# My_esp.net
KiCad netlist of a schematic drawn in Altium Designer
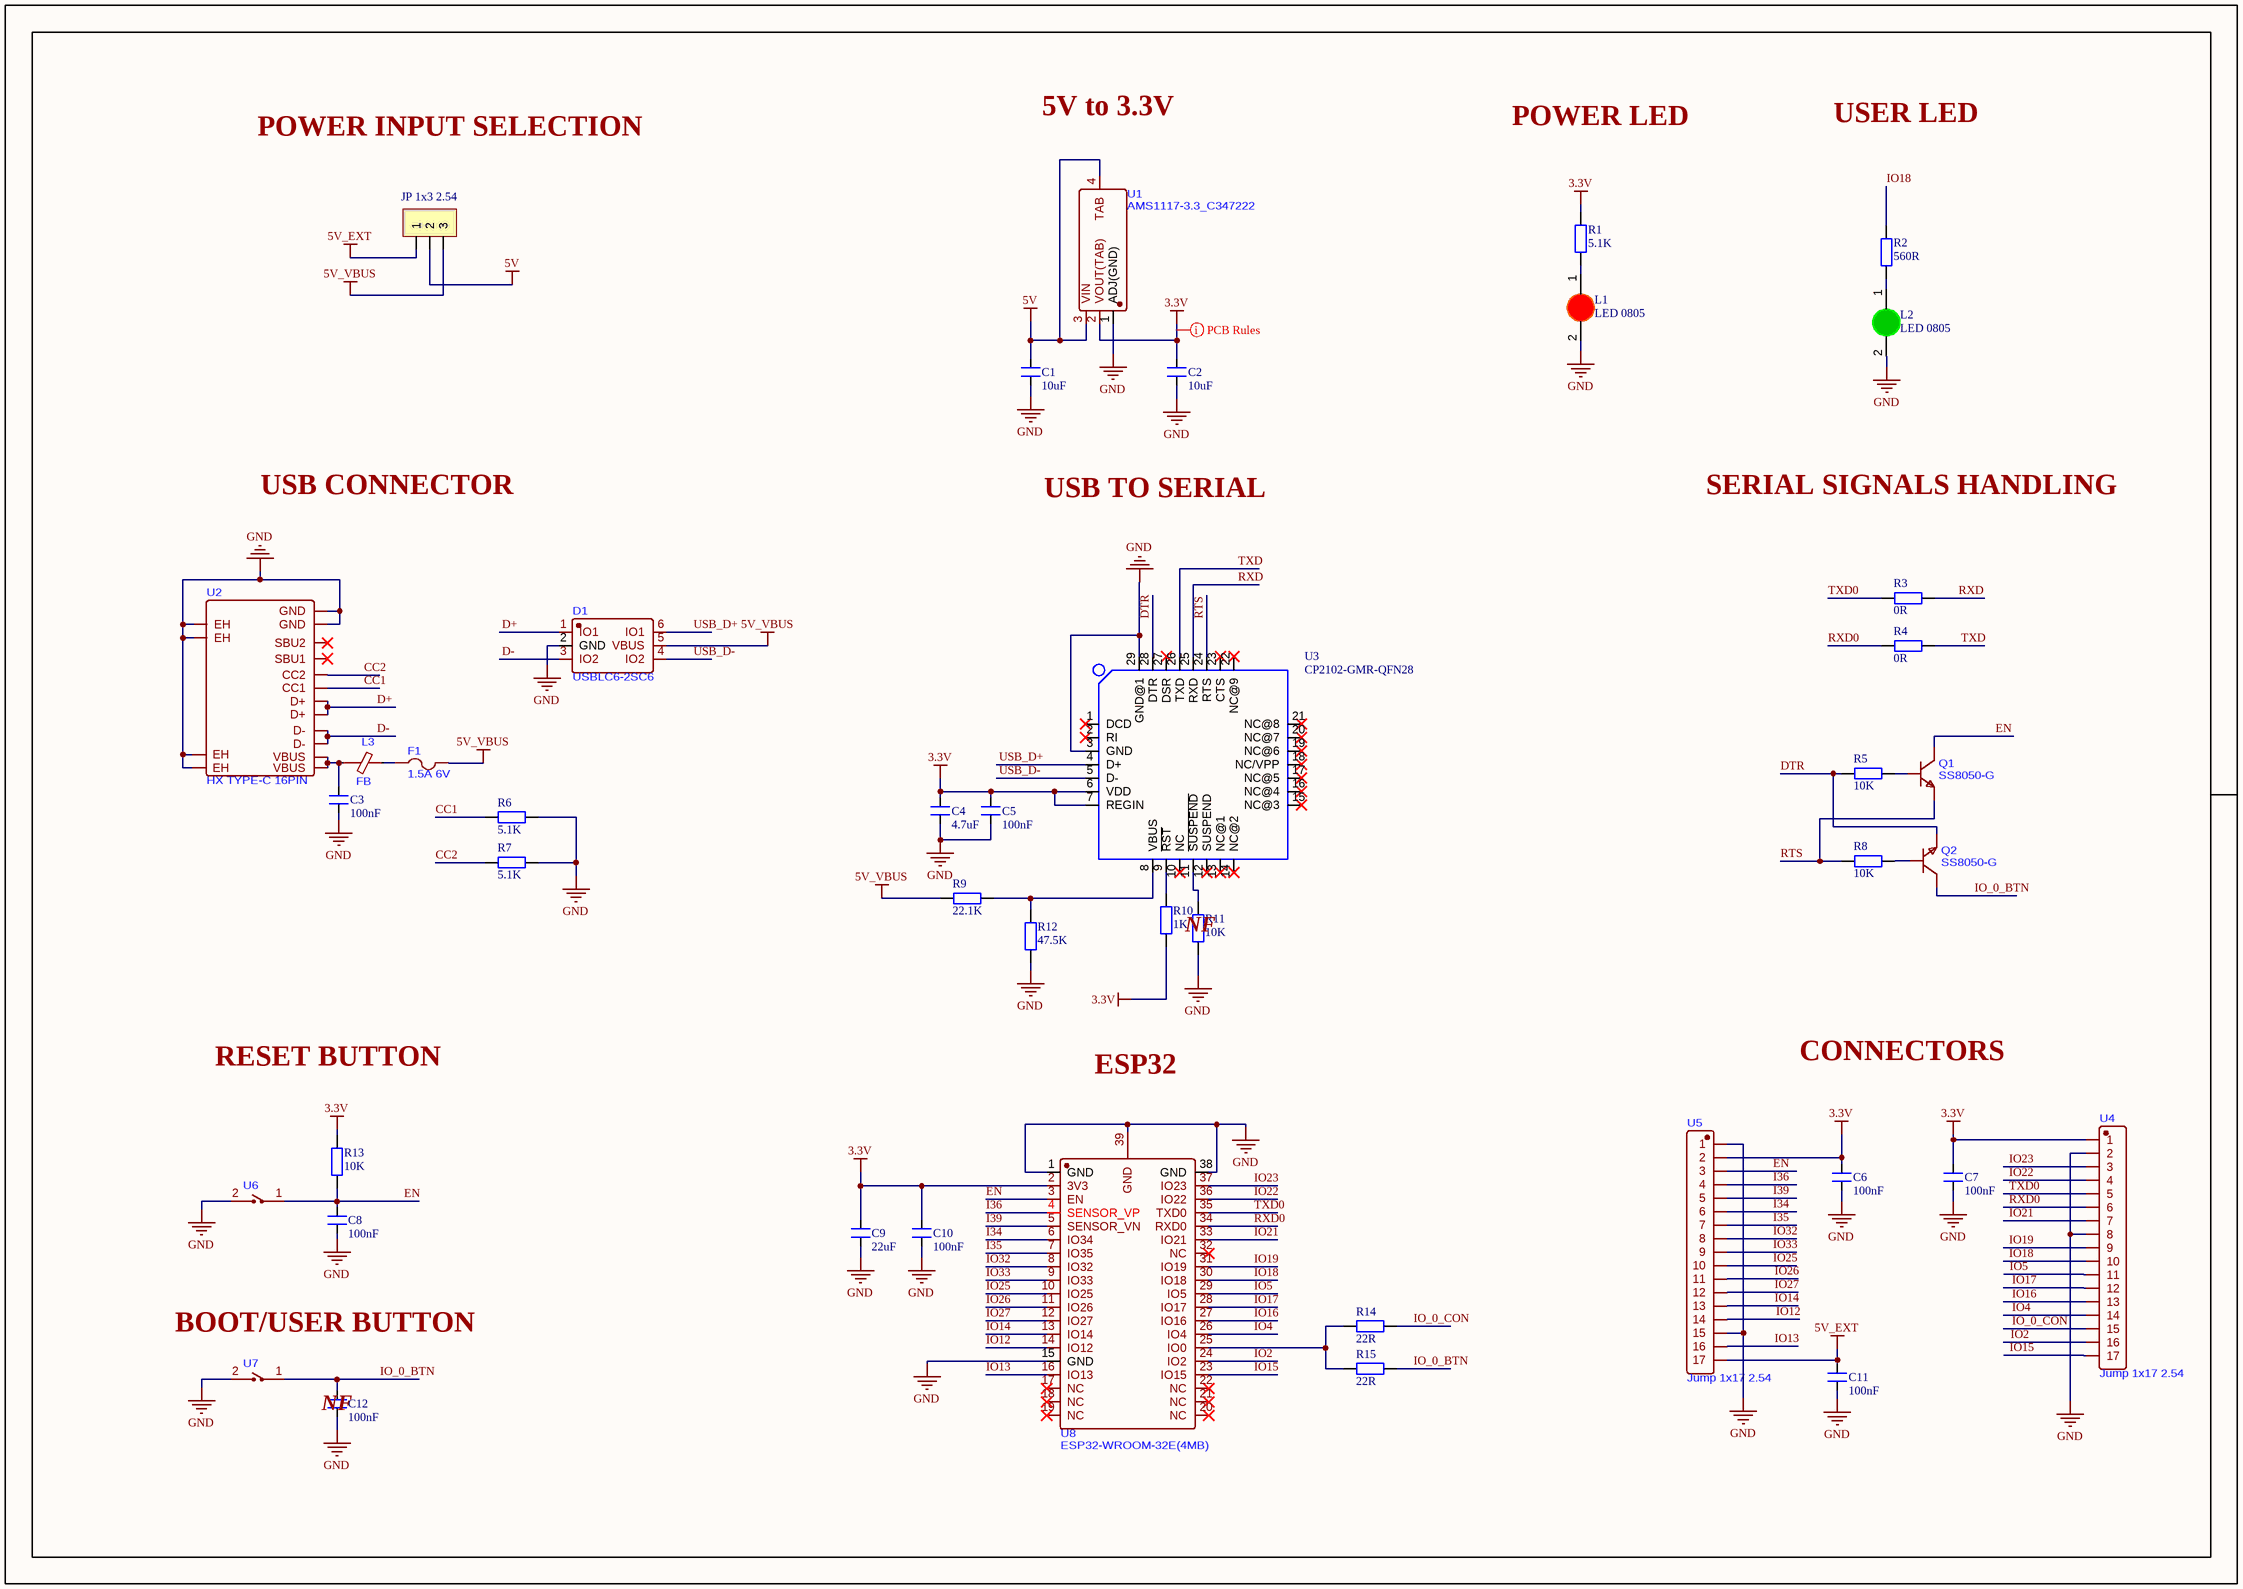
[diagram p0: My_esp.SchDoc]

(export (version "E")
  (design (tool "Eeschema 10.0.6"))
  (components
    (comp (ref "C1")
      (value "10uF")
      (footprint "SM-0805")
      (description "Cap SMD")
      (libsource (lib "My_own_ESP32") (part "Tu"))
    )
    (comp (ref "C2")
      (value "10uF")
      (footprint "SM-0805")
      (description "Cap SMD")
      (libsource (lib "My_own_ESP32") (part "Tu"))
    )
    (comp (ref "C3")
      (value "100nF")
      (footprint "SM-0805")
      (description "Cap SMD")
      (libsource (lib "My_own_ESP32") (part "Tu"))
    )
    (comp (ref "C4")
      (value "4.7uF")
      (footprint "SM-0805")
      (description "Cap SMD")
      (libsource (lib "My_own_ESP32") (part "Tu"))
    )
    (comp (ref "C5")
      (value "100nF")
      (footprint "SM-0805")
      (description "Cap SMD")
      (libsource (lib "My_own_ESP32") (part "Tu"))
    )
    (comp (ref "C6")
      (value "100nF")
      (footprint "SM-0805")
      (description "Cap SMD")
      (libsource (lib "My_own_ESP32") (part "Tu"))
    )
    (comp (ref "C7")
      (value "100nF")
      (footprint "SM-0805")
      (description "Cap SMD")
      (libsource (lib "My_own_ESP32") (part "Tu"))
    )
    (comp (ref "C8")
      (value "100nF")
      (footprint "SM-0805")
      (description "Cap SMD")
      (libsource (lib "My_own_ESP32") (part "Tu"))
    )
    (comp (ref "C9")
      (value "22uF")
      (footprint "SM-0805")
      (description "Cap SMD")
      (libsource (lib "My_own_ESP32") (part "Tu"))
    )
    (comp (ref "C10")
      (value "100nF")
      (footprint "SM-0805")
      (description "Cap SMD")
      (libsource (lib "My_own_ESP32") (part "Tu"))
    )
    (comp (ref "C11")
      (value "100nF")
      (footprint "SM-0805")
      (description "Cap SMD")
      (libsource (lib "My_own_ESP32") (part "Tu"))
    )
    (comp (ref "C12")
      (value "100nF")
      (footprint "SM-0805")
      (description "Cap SMD")
      (libsource (lib "My_own_ESP32") (part "Tu"))
    )
    (comp (ref "D1")
      (value "USBLC6-2SC6")
      (footprint "SOT-23-6_L2.9-W1.6-P0.95-LS2.8-BL")
      (libsource (lib "My_own_ESP32") (part "USBLC6-2SC6"))
    )
    (comp (ref "F1")
      (value "1.5A 6V")
      (footprint "R1206")
      (description "1.5A 6V SMD")
      (libsource (lib "My_own_ESP32") (part "Cau tri tu phuc hoi"))
    )
    (comp (ref "JP1")
      (value "JP 1x3 2.54")
      (footprint "JP 1x3 DT")
      (description "Cắm")
      (libsource (lib "Altium_Lib_by_KhueNguyenCreator") (part "JP 1x3 2.54 Duc Thang"))
    )
    (comp (ref "L1")
      (value "LED 0805")
      (footprint "LED-0805-Red")
      (description "Dán")
      (libsource (lib "Altium_Lib_by_KhueNguyenCreator") (part "LED 0805 Do"))
    )
    (comp (ref "L2")
      (value "LED 0805")
      (footprint "LED-0805-Green")
      (description "Dán")
      (libsource (lib "Altium_Lib_by_KhueNguyenCreator") (part "LED 0805 Xanh La"))
    )
    (comp (ref "L3") (value "FB") (footprint "L0805") (libsource (lib "My_own_ESP32") (part "FerriteBead")))
    (comp (ref "Q1")
      (value "SS8050-G")
      (footprint "SOT-23-3_L2.9-W1.3-P1.90-LS2.4-BR")
      (libsource (lib "My_own_ESP32") (part "SS8050-G"))
    )
    (comp (ref "Q2")
      (value "SS8050-G")
      (footprint "SOT-23-3_L2.9-W1.3-P1.90-LS2.4-BR")
      (libsource (lib "My_own_ESP32") (part "SS8050-G"))
    )
    (comp (ref "R1")
      (value "5.1K")
      (footprint "SM-0805")
      (description "Resistor SMD")
      (libsource (lib "My_own_ESP32") (part "RM"))
    )
    (comp (ref "R2")
      (value "560R")
      (footprint "SM-0805")
      (description "Resistor SMD")
      (libsource (lib "My_own_ESP32") (part "RM"))
    )
    (comp (ref "R3")
      (value "0R")
      (footprint "SM-0805")
      (description "Resistor SMD")
      (libsource (lib "My_own_ESP32") (part "RM"))
    )
    (comp (ref "R4")
      (value "0R")
      (footprint "SM-0805")
      (description "Resistor SMD")
      (libsource (lib "My_own_ESP32") (part "RM"))
    )
    (comp (ref "R5")
      (value "10K")
      (footprint "SM-0805")
      (description "Resistor SMD")
      (libsource (lib "My_own_ESP32") (part "RM"))
    )
    (comp (ref "R6")
      (value "5.1K")
      (footprint "SM-0805")
      (description "Resistor SMD")
      (libsource (lib "My_own_ESP32") (part "RM"))
    )
    (comp (ref "R7")
      (value "5.1K")
      (footprint "SM-0805")
      (description "Resistor SMD")
      (libsource (lib "My_own_ESP32") (part "RM"))
    )
    (comp (ref "R8")
      (value "10K")
      (footprint "SM-0805")
      (description "Resistor SMD")
      (libsource (lib "My_own_ESP32") (part "RM"))
    )
    (comp (ref "R9")
      (value "22.1K")
      (footprint "SM-0805")
      (description "Resistor SMD")
      (libsource (lib "My_own_ESP32") (part "RM"))
    )
    (comp (ref "R10")
      (value "1K")
      (footprint "SM-0805")
      (description "Resistor SMD")
      (libsource (lib "My_own_ESP32") (part "RM"))
    )
    (comp (ref "R11")
      (value "10K")
      (footprint "SM-0805")
      (description "Resistor SMD")
      (libsource (lib "My_own_ESP32") (part "RM"))
    )
    (comp (ref "R12")
      (value "47.5K")
      (footprint "SM-0805")
      (description "Resistor SMD")
      (libsource (lib "My_own_ESP32") (part "RM"))
    )
    (comp (ref "R13")
      (value "10K")
      (footprint "SM-0805")
      (description "Resistor SMD")
      (libsource (lib "My_own_ESP32") (part "RM"))
    )
    (comp (ref "R14")
      (value "22R")
      (footprint "SM-0805")
      (description "Resistor SMD")
      (libsource (lib "My_own_ESP32") (part "RM"))
    )
    (comp (ref "R15")
      (value "22R")
      (footprint "SM-0805")
      (description "Resistor SMD")
      (libsource (lib "My_own_ESP32") (part "RM"))
    )
    (comp (ref "U1")
      (value "AMS1117-3.3_C347222")
      (footprint "SOT-223-4_L6.5-W3.5-P2.30-LS7.0-BR")
      (libsource (lib "My_own_ESP32") (part "AMS1117-3.3_C347222"))
    )
    (comp (ref "U2")
      (value "HX TYPE-C 16PIN")
      (footprint "TYPE-C-SMD_HX-TYPE-C-16PIN")
      (libsource (lib "My_own_ESP32") (part "HX TYPE-C 16PIN"))
    )
    (comp (ref "U3")
      (value "CP2102-GMR-QFN28")
      (footprint "QFN28G_0.5-5X5MM")
      (description "USB Bridge, USB to UART USB 2.0 UART Interface 28-QFN (5x5)")
      (fields (field (name "MP") "CP2102-GMR") (field (name "MF") "Silicon Labs"))
      (libsource (lib "My_own_ESP32") (part "CP2102-GMR-QFN28"))
    )
    (comp (ref "U4")
      (value "Jump 1x17 2.54")
      (footprint "HDR-TH_17P-P2.54-V-M")
      (libsource (lib "My_own_ESP32") (part "Jump 1x17 2.54"))
    )
    (comp (ref "U5")
      (value "Jump 1x17 2.54")
      (footprint "HDR-TH_17P-P2.54-V-M")
      (libsource (lib "My_own_ESP32") (part "Jump 1x17 2.54"))
    )
    (comp (ref "U6")
      (value "Sw 2 chan 3X6X2.5MM")
      (footprint "SW-SMD_L6.1-W3.7-LS8.0")
      (libsource (lib "My_own_ESP32") (part "Sw 2 chan 3X6X2.5MM"))
    )
    (comp (ref "U7")
      (value "Sw 2 chan 3X6X2.5MM")
      (footprint "SW-SMD_L6.1-W3.7-LS8.0")
      (libsource (lib "My_own_ESP32") (part "Sw 2 chan 3X6X2.5MM"))
    )
    (comp (ref "U8")
      (value "ESP32-WROOM-32E(4MB)")
      (footprint "WIFI-SMD_ESP32-WROOM-32E")
      (libsource (lib "My_own_ESP32") (part "ESP32-WROOM-32E(4MB)"))
    )
  )
  (nets
    (net (code "1") (name "/CC1") (class "Default")
      (node (ref "R6") (pin "2") (pinfunction "2_2") (pintype "passive"))
      (node (ref "U2") (pin "A5") (pinfunction "CC1_A5") (pintype "passive"))
    )
    (net (code "2") (name "/CC2") (class "Default")
      (node (ref "R7") (pin "2") (pinfunction "2_2") (pintype "passive"))
      (node (ref "U2") (pin "B5") (pinfunction "CC2_B5") (pintype "passive"))
    )
    (net (code "3") (name "/D+") (class "Default")
      (node (ref "D1") (pin "1") (pinfunction "IO1_1") (pintype "passive"))
      (node (ref "U2") (pin "A6") (pinfunction "D+_A6") (pintype "passive"))
      (node (ref "U2") (pin "B6") (pinfunction "D+_B6") (pintype "passive"))
    )
    (net (code "4") (name "/D-") (class "Default")
      (node (ref "D1") (pin "3") (pinfunction "IO2_3") (pintype "passive"))
      (node (ref "U2") (pin "A7") (pinfunction "D-_A7") (pintype "passive"))
      (node (ref "U2") (pin "B7") (pinfunction "D-_B7") (pintype "passive"))
    )
    (net (code "5") (name "/DTR") (class "Default")
      (node (ref "Q2") (pin "2") (pinfunction "E_2") (pintype "passive"))
      (node (ref "R5") (pin "1") (pinfunction "1_1") (pintype "passive"))
      (node (ref "U3") (pin "28") (pinfunction "DTR_28") (pintype "bidirectional"))
    )
    (net (code "6") (name "/EN") (class "Default")
      (node (ref "C8") (pin "2") (pinfunction "2_2") (pintype "passive"))
      (node (ref "Q1") (pin "3") (pinfunction "C_3") (pintype "passive"))
      (node (ref "R13") (pin "1") (pinfunction "1_1") (pintype "passive"))
      (node (ref "U5") (pin "3") (pinfunction "3_3") (pintype "passive"))
      (node (ref "U6") (pin "1") (pinfunction "1_1") (pintype "passive"))
      (node (ref "U8") (pin "3") (pinfunction "EN_3") (pintype "passive"))
    )
    (net (code "7") (name "/I34") (class "Default")
      (node (ref "U5") (pin "6") (pinfunction "6_6") (pintype "passive"))
      (node (ref "U8") (pin "6") (pinfunction "IO34_6") (pintype "passive"))
    )
    (net (code "8") (name "/I35") (class "Default")
      (node (ref "U5") (pin "7") (pinfunction "7_7") (pintype "passive"))
      (node (ref "U8") (pin "7") (pinfunction "IO35_7") (pintype "passive"))
    )
    (net (code "9") (name "/I36") (class "Default")
      (node (ref "U5") (pin "4") (pinfunction "4_4") (pintype "passive"))
      (node (ref "U8") (pin "4") (pinfunction "SENSOR_VP_4") (pintype "passive"))
    )
    (net (code "10") (name "/I39") (class "Default")
      (node (ref "U5") (pin "5") (pinfunction "5_5") (pintype "passive"))
      (node (ref "U8") (pin "5") (pinfunction "SENSOR_VN_5") (pintype "passive"))
    )
    (net (code "11") (name "/IO2") (class "Default")
      (node (ref "U4") (pin "16") (pinfunction "16_16") (pintype "passive"))
      (node (ref "U8") (pin "24") (pinfunction "IO2_24") (pintype "passive"))
    )
    (net (code "12") (name "/IO4") (class "Default")
      (node (ref "U4") (pin "14") (pinfunction "14_14") (pintype "passive"))
      (node (ref "U8") (pin "26") (pinfunction "IO4_26") (pintype "passive"))
    )
    (net (code "13") (name "/IO5") (class "Default")
      (node (ref "U4") (pin "11") (pinfunction "11_11") (pintype "passive"))
      (node (ref "U8") (pin "29") (pinfunction "IO5_29") (pintype "passive"))
    )
    (net (code "14") (name "/IO12") (class "Default")
      (node (ref "U5") (pin "14") (pinfunction "14_14") (pintype "passive"))
      (node (ref "U8") (pin "14") (pinfunction "IO12_14") (pintype "passive"))
    )
    (net (code "15") (name "/IO13") (class "Default")
      (node (ref "U5") (pin "16") (pinfunction "16_16") (pintype "passive"))
      (node (ref "U8") (pin "16") (pinfunction "IO13_16") (pintype "passive"))
    )
    (net (code "16") (name "/IO14") (class "Default")
      (node (ref "U5") (pin "13") (pinfunction "13_13") (pintype "passive"))
      (node (ref "U8") (pin "13") (pinfunction "IO14_13") (pintype "passive"))
    )
    (net (code "17") (name "/IO15") (class "Default")
      (node (ref "U4") (pin "17") (pinfunction "17_17") (pintype "passive"))
      (node (ref "U8") (pin "23") (pinfunction "IO15_23") (pintype "passive"))
    )
    (net (code "18") (name "/IO16") (class "Default")
      (node (ref "U4") (pin "13") (pinfunction "13_13") (pintype "passive"))
      (node (ref "U8") (pin "27") (pinfunction "IO16_27") (pintype "passive"))
    )
    (net (code "19") (name "/IO17") (class "Default")
      (node (ref "U4") (pin "12") (pinfunction "12_12") (pintype "passive"))
      (node (ref "U8") (pin "28") (pinfunction "IO17_28") (pintype "passive"))
    )
    (net (code "20") (name "/IO18") (class "Default")
      (node (ref "R2") (pin "1") (pinfunction "1_1") (pintype "passive"))
      (node (ref "U4") (pin "10") (pinfunction "10_10") (pintype "passive"))
      (node (ref "U8") (pin "30") (pinfunction "IO18_30") (pintype "passive"))
    )
    (net (code "21") (name "/IO19") (class "Default")
      (node (ref "U4") (pin "9") (pinfunction "9_9") (pintype "passive"))
      (node (ref "U8") (pin "31") (pinfunction "IO19_31") (pintype "passive"))
    )
    (net (code "22") (name "/IO21") (class "Default")
      (node (ref "U4") (pin "7") (pinfunction "7_7") (pintype "passive"))
      (node (ref "U8") (pin "33") (pinfunction "IO21_33") (pintype "passive"))
    )
    (net (code "23") (name "/IO22") (class "Default")
      (node (ref "U4") (pin "4") (pinfunction "4_4") (pintype "passive"))
      (node (ref "U8") (pin "36") (pinfunction "IO22_36") (pintype "passive"))
    )
    (net (code "24") (name "/IO23") (class "Default")
      (node (ref "U4") (pin "3") (pinfunction "3_3") (pintype "passive"))
      (node (ref "U8") (pin "37") (pinfunction "IO23_37") (pintype "passive"))
    )
    (net (code "25") (name "/IO25") (class "Default")
      (node (ref "U5") (pin "10") (pinfunction "10_10") (pintype "passive"))
      (node (ref "U8") (pin "10") (pinfunction "IO25_10") (pintype "passive"))
    )
    (net (code "26") (name "/IO26") (class "Default")
      (node (ref "U5") (pin "11") (pinfunction "11_11") (pintype "passive"))
      (node (ref "U8") (pin "11") (pinfunction "IO26_11") (pintype "passive"))
    )
    (net (code "27") (name "/IO27") (class "Default")
      (node (ref "U5") (pin "12") (pinfunction "12_12") (pintype "passive"))
      (node (ref "U8") (pin "12") (pinfunction "IO27_12") (pintype "passive"))
    )
    (net (code "28") (name "/IO32") (class "Default")
      (node (ref "U5") (pin "8") (pinfunction "8_8") (pintype "passive"))
      (node (ref "U8") (pin "8") (pinfunction "IO32_8") (pintype "passive"))
    )
    (net (code "29") (name "/IO33") (class "Default")
      (node (ref "U5") (pin "9") (pinfunction "9_9") (pintype "passive"))
      (node (ref "U8") (pin "9") (pinfunction "IO33_9") (pintype "passive"))
    )
    (net (code "30") (name "/IO_0_BTN") (class "Default")
      (node (ref "C12") (pin "2") (pinfunction "2_2") (pintype "passive"))
      (node (ref "Q2") (pin "3") (pinfunction "C_3") (pintype "passive"))
      (node (ref "R15") (pin "2") (pinfunction "2_2") (pintype "passive"))
      (node (ref "U7") (pin "1") (pinfunction "1_1") (pintype "passive"))
    )
    (net (code "31") (name "/IO_0_CON") (class "Default")
      (node (ref "R14") (pin "2") (pinfunction "2_2") (pintype "passive"))
      (node (ref "U4") (pin "15") (pinfunction "15_15") (pintype "passive"))
    )
    (net (code "32") (name "/RTS") (class "Default")
      (node (ref "Q1") (pin "2") (pinfunction "E_2") (pintype "passive"))
      (node (ref "R8") (pin "1") (pinfunction "1_1") (pintype "passive"))
      (node (ref "U3") (pin "24") (pinfunction "RTS_24") (pintype "bidirectional"))
    )
    (net (code "33") (name "/RXD") (class "Default")
      (node (ref "R3") (pin "2") (pinfunction "2_2") (pintype "passive"))
      (node (ref "U3") (pin "25") (pinfunction "RXD_25") (pintype "bidirectional"))
    )
    (net (code "34") (name "/RXD0") (class "Default")
      (node (ref "R4") (pin "1") (pinfunction "1_1") (pintype "passive"))
      (node (ref "U4") (pin "6") (pinfunction "6_6") (pintype "passive"))
      (node (ref "U8") (pin "34") (pinfunction "RXD0_34") (pintype "passive"))
    )
    (net (code "35") (name "/TXD") (class "Default")
      (node (ref "R4") (pin "2") (pinfunction "2_2") (pintype "passive"))
      (node (ref "U3") (pin "26") (pinfunction "TXD_26") (pintype "bidirectional"))
    )
    (net (code "36") (name "/TXD0") (class "Default")
      (node (ref "R3") (pin "1") (pinfunction "1_1") (pintype "passive"))
      (node (ref "U4") (pin "5") (pinfunction "5_5") (pintype "passive"))
      (node (ref "U8") (pin "35") (pinfunction "TXD0_35") (pintype "passive"))
    )
    (net (code "37") (name "/USB_D+") (class "Default")
      (node (ref "D1") (pin "6") (pinfunction "IO1_6") (pintype "passive"))
      (node (ref "U3") (pin "4") (pinfunction "D+_4") (pintype "bidirectional"))
    )
    (net (code "38") (name "/USB_D-") (class "Default")
      (node (ref "D1") (pin "4") (pinfunction "IO2_4") (pintype "passive"))
      (node (ref "U3") (pin "5") (pinfunction "D-_5") (pintype "bidirectional"))
    )
    (net (code "39") (name "3.3V") (class "Default")
      (node (ref "C10") (pin "2") (pinfunction "2_2") (pintype "passive"))
      (node (ref "C2") (pin "2") (pinfunction "2_2") (pintype "passive"))
      (node (ref "C4") (pin "2") (pinfunction "2_2") (pintype "passive"))
      (node (ref "C5") (pin "2") (pinfunction "2_2") (pintype "passive"))
      (node (ref "C6") (pin "2") (pinfunction "2_2") (pintype "passive"))
      (node (ref "C7") (pin "2") (pinfunction "2_2") (pintype "passive"))
      (node (ref "C9") (pin "2") (pinfunction "2_2") (pintype "passive"))
      (node (ref "R1") (pin "1") (pinfunction "1_1") (pintype "passive"))
      (node (ref "R10") (pin "1") (pinfunction "1_1") (pintype "passive"))
      (node (ref "R13") (pin "2") (pinfunction "2_2") (pintype "passive"))
      (node (ref "U1") (pin "2") (pinfunction "VOUT(TAB)_2") (pintype "passive"))
      (node (ref "U3") (pin "6") (pinfunction "VDD_6") (pintype "bidirectional"))
      (node (ref "U3") (pin "7") (pinfunction "REGIN_7") (pintype "bidirectional"))
      (node (ref "U4") (pin "1") (pinfunction "1_1") (pintype "passive"))
      (node (ref "U5") (pin "2") (pinfunction "2_2") (pintype "passive"))
      (node (ref "U8") (pin "2") (pinfunction "3V3_2") (pintype "passive"))
    )
    (net (code "40") (name "5V") (class "Default")
      (node (ref "C1") (pin "2") (pinfunction "2_2") (pintype "passive"))
      (node (ref "JP1") (pin "2") (pinfunction "2_2") (pintype "passive"))
      (node (ref "U1") (pin "3") (pinfunction "VIN_3") (pintype "passive"))
      (node (ref "U1") (pin "4") (pinfunction "TAB_4") (pintype "passive"))
    )
    (net (code "41") (name "5V_EXT") (class "Default")
      (node (ref "C11") (pin "2") (pinfunction "2_2") (pintype "passive"))
      (node (ref "JP1") (pin "1") (pinfunction "1_1") (pintype "passive"))
      (node (ref "U5") (pin "17") (pinfunction "17_17") (pintype "passive"))
    )
    (net (code "42") (name "5V_VBUS") (class "Default")
      (node (ref "D1") (pin "5") (pinfunction "VBUS_5") (pintype "passive"))
      (node (ref "F1") (pin "2") (pinfunction "2_2") (pintype "passive"))
      (node (ref "JP1") (pin "3") (pinfunction "3_3") (pintype "passive"))
      (node (ref "R9") (pin "2") (pinfunction "2_2") (pintype "passive"))
    )
    (net (code "43") (name "GND") (class "Default")
      (node (ref "C1") (pin "1") (pinfunction "1_1") (pintype "passive"))
      (node (ref "C10") (pin "1") (pinfunction "1_1") (pintype "passive"))
      (node (ref "C11") (pin "1") (pinfunction "1_1") (pintype "passive"))
      (node (ref "C12") (pin "1") (pinfunction "1_1") (pintype "passive"))
      (node (ref "C2") (pin "1") (pinfunction "1_1") (pintype "passive"))
      (node (ref "C3") (pin "1") (pinfunction "1_1") (pintype "passive"))
      (node (ref "C4") (pin "1") (pinfunction "1_1") (pintype "passive"))
      (node (ref "C5") (pin "1") (pinfunction "1_1") (pintype "passive"))
      (node (ref "C6") (pin "1") (pinfunction "1_1") (pintype "passive"))
      (node (ref "C7") (pin "1") (pinfunction "1_1") (pintype "passive"))
      (node (ref "C8") (pin "1") (pinfunction "1_1") (pintype "passive"))
      (node (ref "C9") (pin "1") (pinfunction "1_1") (pintype "passive"))
      (node (ref "D1") (pin "2") (pinfunction "GND_2") (pintype "passive"))
      (node (ref "L1") (pin "2") (pinfunction "K_2") (pintype "passive"))
      (node (ref "L2") (pin "2") (pinfunction "K_2") (pintype "passive"))
      (node (ref "R11") (pin "1") (pinfunction "1_1") (pintype "passive"))
      (node (ref "R12") (pin "1") (pinfunction "1_1") (pintype "passive"))
      (node (ref "R6") (pin "1") (pinfunction "1_1") (pintype "passive"))
      (node (ref "R7") (pin "1") (pinfunction "1_1") (pintype "passive"))
      (node (ref "U1") (pin "1") (pinfunction "ADJ(GND)_1") (pintype "passive"))
      (node (ref "U2") (pin "17") (pinfunction "EH_17") (pintype "passive"))
      (node (ref "U2") (pin "18") (pinfunction "EH_18") (pintype "passive"))
      (node (ref "U2") (pin "19") (pinfunction "EH_19") (pintype "passive"))
      (node (ref "U2") (pin "20") (pinfunction "EH_20") (pintype "passive"))
      (node (ref "U2") (pin "A12B1") (pinfunction "GND_A12B1") (pintype "passive"))
      (node (ref "U2") (pin "B12A1") (pinfunction "GND_B12A1") (pintype "passive"))
      (node (ref "U3") (pin "29") (pinfunction "GND@1_29") (pintype "bidirectional"))
      (node (ref "U3") (pin "3") (pinfunction "GND_3") (pintype "bidirectional"))
      (node (ref "U4") (pin "2") (pinfunction "2_2") (pintype "passive"))
      (node (ref "U4") (pin "8") (pinfunction "8_8") (pintype "passive"))
      (node (ref "U5") (pin "1") (pinfunction "1_1") (pintype "passive"))
      (node (ref "U5") (pin "15") (pinfunction "15_15") (pintype "passive"))
      (node (ref "U6") (pin "2") (pinfunction "2_2") (pintype "passive"))
      (node (ref "U7") (pin "2") (pinfunction "2_2") (pintype "passive"))
      (node (ref "U8") (pin "1") (pinfunction "GND_1") (pintype "passive"))
      (node (ref "U8") (pin "15") (pinfunction "GND_15") (pintype "passive"))
      (node (ref "U8") (pin "38") (pinfunction "GND_38") (pintype "passive"))
      (node (ref "U8") (pin "39") (pinfunction "GND_39") (pintype "passive"))
    )
    (net (code "44") (name "Net-(C3-Pad2)") (class "Default")
      (node (ref "C3") (pin "2") (pinfunction "2_2") (pintype "passive"))
      (node (ref "L3") (pin "2") (pinfunction "2_2") (pintype "passive"))
      (node (ref "U2") (pin "A9B4") (pinfunction "VBUS_A9B4") (pintype "passive"))
      (node (ref "U2") (pin "B9A4") (pinfunction "VBUS_B9A4") (pintype "passive"))
    )
    (net (code "45") (name "Net-(F1-Pad1)") (class "Default")
      (node (ref "F1") (pin "1") (pinfunction "1_1") (pintype "passive"))
      (node (ref "L3") (pin "1") (pinfunction "1_1") (pintype "passive"))
    )
    (net (code "46") (name "Net-(L1-A)") (class "Default")
      (node (ref "L1") (pin "1") (pinfunction "A_1") (pintype "passive"))
      (node (ref "R1") (pin "2") (pinfunction "2_2") (pintype "passive"))
    )
    (net (code "47") (name "Net-(L2-A)") (class "Default")
      (node (ref "L2") (pin "1") (pinfunction "A_1") (pintype "passive"))
      (node (ref "R2") (pin "2") (pinfunction "2_2") (pintype "passive"))
    )
    (net (code "48") (name "Net-(Q1-B)") (class "Default")
      (node (ref "Q1") (pin "1") (pinfunction "B_1") (pintype "passive"))
      (node (ref "R5") (pin "2") (pinfunction "2_2") (pintype "passive"))
    )
    (net (code "49") (name "Net-(Q2-B)") (class "Default")
      (node (ref "Q2") (pin "1") (pinfunction "B_1") (pintype "passive"))
      (node (ref "R8") (pin "2") (pinfunction "2_2") (pintype "passive"))
    )
    (net (code "50") (name "Net-(U3-VBUS)") (class "Default")
      (node (ref "R12") (pin "2") (pinfunction "2_2") (pintype "passive"))
      (node (ref "R9") (pin "1") (pinfunction "1_1") (pintype "passive"))
      (node (ref "U3") (pin "8") (pinfunction "VBUS_8") (pintype "bidirectional"))
    )
    (net (code "51") (name "Net-(U3-~{RST})") (class "Default")
      (node (ref "R10") (pin "2") (pinfunction "2_2") (pintype "passive"))
      (node (ref "U3") (pin "9") (pinfunction "~{RST}_9") (pintype "bidirectional"))
    )
    (net (code "52") (name "Net-(U3-~{SUSPEND})") (class "Default")
      (node (ref "R11") (pin "2") (pinfunction "2_2") (pintype "passive"))
      (node (ref "U3") (pin "11") (pinfunction "~{SUSPEND}_11") (pintype "bidirectional"))
    )
    (net (code "53") (name "Net-(U8-IO0)") (class "Default")
      (node (ref "R14") (pin "1") (pinfunction "1_1") (pintype "passive"))
      (node (ref "R15") (pin "1") (pinfunction "1_1") (pintype "passive"))
      (node (ref "U8") (pin "25") (pinfunction "IO0_25") (pintype "passive"))
    )
    (net (code "54") (name "unconnected-(U2-SBU1-PadA8)") (class "Default")
      (node (ref "U2") (pin "A8") (pinfunction "SBU1_A8") (pintype "passive+no_connect"))
    )
    (net (code "55") (name "unconnected-(U2-SBU2-PadB8)") (class "Default")
      (node (ref "U2") (pin "B8") (pinfunction "SBU2_B8") (pintype "passive+no_connect"))
    )
    (net (code "56") (name "unconnected-(U3-CTS-Pad23)") (class "Default")
      (node (ref "U3") (pin "23") (pinfunction "CTS_23") (pintype "bidirectional+no_connect"))
    )
    (net (code "57") (name "unconnected-(U3-DCD-Pad1)") (class "Default")
      (node (ref "U3") (pin "1") (pinfunction "DCD_1") (pintype "bidirectional+no_connect"))
    )
    (net (code "58") (name "unconnected-(U3-DSR-Pad27)") (class "Default")
      (node (ref "U3") (pin "27") (pinfunction "DSR_27") (pintype "bidirectional+no_connect"))
    )
    (net (code "59") (name "unconnected-(U3-NC-Pad10)") (class "Default")
      (node (ref "U3") (pin "10") (pinfunction "NC_10") (pintype "bidirectional+no_connect"))
    )
    (net (code "60") (name "unconnected-(U3-NC@1-Pad13)") (class "Default")
      (node (ref "U3") (pin "13") (pinfunction "NC@1_13") (pintype "bidirectional+no_connect"))
    )
    (net (code "61") (name "unconnected-(U3-NC@2-Pad14)") (class "Default")
      (node (ref "U3") (pin "14") (pinfunction "NC@2_14") (pintype "bidirectional+no_connect"))
    )
    (net (code "62") (name "unconnected-(U3-NC@3-Pad15)") (class "Default")
      (node (ref "U3") (pin "15") (pinfunction "NC@3_15") (pintype "bidirectional+no_connect"))
    )
    (net (code "63") (name "unconnected-(U3-NC@4-Pad16)") (class "Default")
      (node (ref "U3") (pin "16") (pinfunction "NC@4_16") (pintype "bidirectional+no_connect"))
    )
    (net (code "64") (name "unconnected-(U3-NC@5-Pad17)") (class "Default")
      (node (ref "U3") (pin "17") (pinfunction "NC@5_17") (pintype "bidirectional+no_connect"))
    )
    (net (code "65") (name "unconnected-(U3-NC@6-Pad19)") (class "Default")
      (node (ref "U3") (pin "19") (pinfunction "NC@6_19") (pintype "bidirectional+no_connect"))
    )
    (net (code "66") (name "unconnected-(U3-NC@7-Pad20)") (class "Default")
      (node (ref "U3") (pin "20") (pinfunction "NC@7_20") (pintype "bidirectional+no_connect"))
    )
    (net (code "67") (name "unconnected-(U3-NC@8-Pad21)") (class "Default")
      (node (ref "U3") (pin "21") (pinfunction "NC@8_21") (pintype "bidirectional+no_connect"))
    )
    (net (code "68") (name "unconnected-(U3-NC@9-Pad22)") (class "Default")
      (node (ref "U3") (pin "22") (pinfunction "NC@9_22") (pintype "bidirectional+no_connect"))
    )
    (net (code "69") (name "unconnected-(U3-NC{slash}VPP-Pad18)") (class "Default")
      (node (ref "U3") (pin "18") (pinfunction "NC/VPP_18") (pintype "bidirectional+no_connect"))
    )
    (net (code "70") (name "unconnected-(U3-RI-Pad2)") (class "Default")
      (node (ref "U3") (pin "2") (pinfunction "RI_2") (pintype "bidirectional+no_connect"))
    )
    (net (code "71") (name "unconnected-(U3-SUSPEND-Pad12)") (class "Default")
      (node (ref "U3") (pin "12") (pinfunction "SUSPEND_12") (pintype "bidirectional+no_connect"))
    )
    (net (code "72") (name "unconnected-(U8-NC-Pad17)") (class "Default")
      (node (ref "U8") (pin "17") (pinfunction "NC_17") (pintype "passive+no_connect"))
    )
    (net (code "73") (name "unconnected-(U8-NC-Pad18)") (class "Default")
      (node (ref "U8") (pin "18") (pinfunction "NC_18") (pintype "passive+no_connect"))
    )
    (net (code "74") (name "unconnected-(U8-NC-Pad19)") (class "Default")
      (node (ref "U8") (pin "19") (pinfunction "NC_19") (pintype "passive+no_connect"))
    )
    (net (code "75") (name "unconnected-(U8-NC-Pad20)") (class "Default")
      (node (ref "U8") (pin "20") (pinfunction "NC_20") (pintype "passive+no_connect"))
    )
    (net (code "76") (name "unconnected-(U8-NC-Pad21)") (class "Default")
      (node (ref "U8") (pin "21") (pinfunction "NC_21") (pintype "passive+no_connect"))
    )
    (net (code "77") (name "unconnected-(U8-NC-Pad22)") (class "Default")
      (node (ref "U8") (pin "22") (pinfunction "NC_22") (pintype "passive+no_connect"))
    )
    (net (code "78") (name "unconnected-(U8-NC-Pad32)") (class "Default")
      (node (ref "U8") (pin "32") (pinfunction "NC_32") (pintype "passive+no_connect"))
    )
  )
)
